# Main_Display_Module_ESP32.net
KiCad netlist of a schematic drawn in Altium Designer
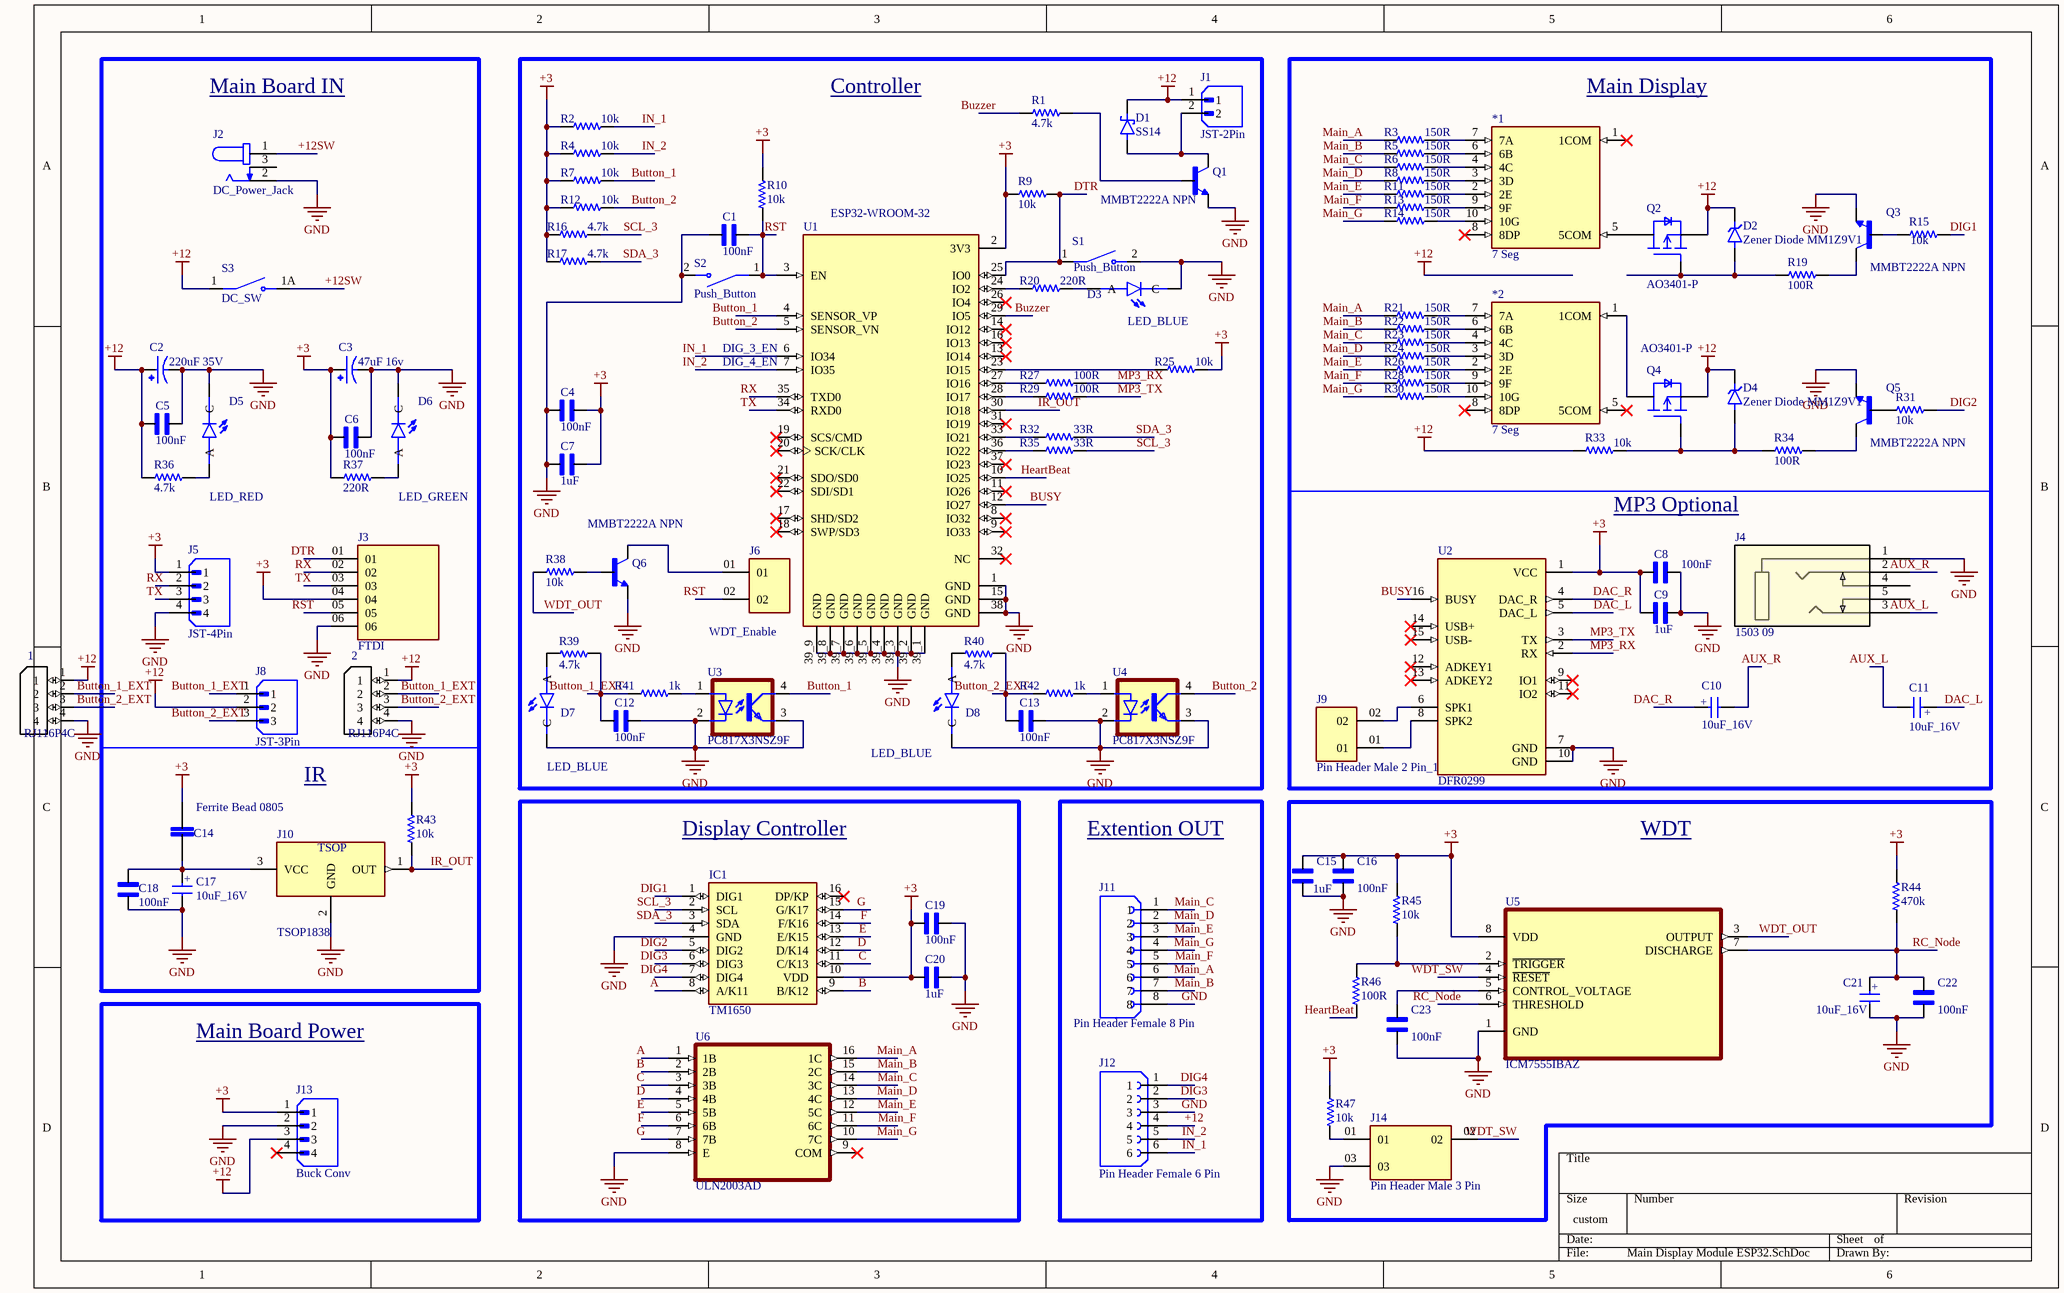
[diagram p0: Main Display Module ESP32.SchDoc]

(export (version "E")
  (design (tool "Eeschema 10.0.6"))
  (components
    (comp (ref "*1") (value "7 Seg") (footprint "2.3_7-SEG_DIS") (libsource (lib "Modules") (part "7 Seg")))
    (comp (ref "*2") (value "7 Seg") (footprint "2.3_7-SEG_DIS") (libsource (lib "Modules") (part "7 Seg")))
    (comp (ref "1")
      (value "RJ116P4C")
      (footprint "*RJ6P4C")
      (fields (field (name "MF") "TE Connectivity / Raychem") (field (name "MP") "RJ11-6P4C"))
      (libsource (lib "RJ116P4C") (part "RJ116P4C"))
    )
    (comp (ref "2")
      (value "RJ116P4C")
      (footprint "*RJ6P4C")
      (fields (field (name "MF") "TE Connectivity / Raychem") (field (name "MP") "RJ11-6P4C"))
      (libsource (lib "RJ116P4C") (part "RJ116P4C"))
    )
    (comp (ref "C1")
      (value "100nF")
      (footprint "Capacitor 0805")
      (description "0.1 ÂµF Â±10% 50V Ceramic Capacitor X7R 0805 (2012 Metric)")
      (fields (field (name "MF") "Murata") (field (name "MP") "GCE21BR71H104KA01L"))
      (libsource (lib "") (part "Capacitor 0805_1"))
    )
    (comp (ref "C2")
      (value "220uF 35V")
      (footprint "220uF 35V")
      (description "220ÂµF 35V Aluminum Electrolytic Capacitors Radial, Can - SMD 2000 Hrs @ 85Â°C")
      (fields (field (name "MP") "EEE1VA221P") (field (name "MF") "Panasonic"))
      (libsource (lib "Capacitors") (part "220uF 35V"))
    )
    (comp (ref "C3")
      (value "47uF 16v")
      (footprint "47uf 16v")
      (description "47ÂµF 16V Aluminum Electrolytic Capacitors Radial, Can - SMD 1000 Hrs @ 105Â°C")
      (fields (field (name "MF") "Panasonic") (field (name "MP") "EEE-HA1C470P"))
      (libsource (lib "Capacitors") (part "47uF 16v"))
    )
    (comp (ref "C4")
      (value "100nF")
      (footprint "Capacitor 0805")
      (description "0.1 ÂµF Â±10% 50V Ceramic Capacitor X7R 0805 (2012 Metric)")
      (fields (field (name "MF") "Murata") (field (name "MP") "GCE21BR71H104KA01L"))
      (libsource (lib "") (part "Capacitor 0805_1"))
    )
    (comp (ref "C5")
      (value "100nF")
      (footprint "Capacitor 0805")
      (description "0.1 ÂµF Â±10% 50V Ceramic Capacitor X7R 0805 (2012 Metric)")
      (fields (field (name "MF") "Murata") (field (name "MP") "GCE21BR71H104KA01L"))
      (libsource (lib "") (part "Capacitor 0805_1"))
    )
    (comp (ref "C6")
      (value "100nF")
      (footprint "Capacitor 0805")
      (description "0.1 ÂµF Â±10% 50V Ceramic Capacitor X7R 0805 (2012 Metric)")
      (fields (field (name "MF") "Murata") (field (name "MP") "GCE21BR71H104KA01L"))
      (libsource (lib "") (part "Capacitor 0805_1"))
    )
    (comp (ref "C7")
      (value "1uF")
      (footprint "Capacitor 0805")
      (description "0.1 ÂµF Â±10% 50V Ceramic Capacitor X7R 0805 (2012 Metric)")
      (fields (field (name "MF") "Murata") (field (name "MP") "GCE21BR71H104KA01L"))
      (libsource (lib "") (part "Capacitor 0805_1"))
    )
    (comp (ref "C8")
      (value "100nF")
      (footprint "Capacitor 0805")
      (description "0.1 ÂµF Â±10% 50V Ceramic Capacitor X7R 0805 (2012 Metric)")
      (fields (field (name "MF") "Murata") (field (name "MP") "GCE21BR71H104KA01L"))
      (libsource (lib "") (part "Capacitor 0805_1"))
    )
    (comp (ref "C9")
      (value "1uF")
      (footprint "Capacitor 0805")
      (description "0.1 ÂµF Â±10% 50V Ceramic Capacitor X7R 0805 (2012 Metric)")
      (fields (field (name "MF") "Murata") (field (name "MP") "GCE21BR71H104KA01L"))
      (libsource (lib "") (part "Capacitor 0805_1"))
    )
    (comp (ref "C10")
      (value "10uF_16V")
      (footprint "10uF_16V")
      (fields (field (name "MF") "WÃ¼rth Elektronik") (field (name "MP") "865090368008"))
      (libsource (lib "Capacitors") (part "10uF_16V"))
    )
    (comp (ref "C11")
      (value "10uF_16V")
      (footprint "10uF_16V")
      (fields (field (name "MF") "WÃ¼rth Elektronik") (field (name "MP") "865090368008"))
      (libsource (lib "Capacitors") (part "10uF_16V"))
    )
    (comp (ref "C12")
      (value "100nF")
      (footprint "Capacitor 0805")
      (description "0.1 ÂµF Â±10% 50V Ceramic Capacitor X7R 0805 (2012 Metric)")
      (fields (field (name "MF") "Murata") (field (name "MP") "GCE21BR71H104KA01L"))
      (libsource (lib "Capacitors") (part "Capacitor 0805"))
    )
    (comp (ref "C13")
      (value "100nF")
      (footprint "Capacitor 0805")
      (description "0.1 ÂµF Â±10% 50V Ceramic Capacitor X7R 0805 (2012 Metric)")
      (fields (field (name "MF") "Murata") (field (name "MP") "GCE21BR71H104KA01L"))
      (libsource (lib "") (part "Capacitor 0805_1"))
    )
    (comp (ref "C14")
      (value "Ferrite Bead 0805")
      (footprint "Ferrite Bead 0805")
      (description "BLM Series 0805 1 kOhm 200 mA 0.45 DCR Surface Mount Ferrite Bead")
      (fields (field (name "MF") "Murata") (field (name "MP") "BLM21AH102SN1D"))
      (libsource (lib "Resistors") (part "Ferrite Bead 0805"))
    )
    (comp (ref "C15")
      (value "1uF")
      (footprint "Capacitor 0805")
      (description "0.1 ÂµF Â±10% 50V Ceramic Capacitor X7R 0805 (2012 Metric)")
      (fields (field (name "MF") "Murata") (field (name "MP") "GCE21BR71H104KA01L"))
      (libsource (lib "") (part "Capacitor 0805_2"))
    )
    (comp (ref "C16")
      (value "100nF")
      (footprint "Capacitor 0805")
      (description "0.1 ÂµF Â±10% 50V Ceramic Capacitor X7R 0805 (2012 Metric)")
      (fields (field (name "MF") "Murata") (field (name "MP") "GCE21BR71H104KA01L"))
      (libsource (lib "") (part "Capacitor 0805_2"))
    )
    (comp (ref "C17")
      (value "10uF_16V")
      (footprint "10uF_16V")
      (fields (field (name "MF") "WÃ¼rth Elektronik") (field (name "MP") "865090368008"))
      (libsource (lib "Capacitors") (part "10uF_16V"))
    )
    (comp (ref "C18")
      (value "100nF")
      (footprint "Capacitor 0805")
      (description "0.1 ÂµF Â±10% 50V Ceramic Capacitor X7R 0805 (2012 Metric)")
      (fields (field (name "MF") "Murata") (field (name "MP") "GCE21BR71H104KA01L"))
      (libsource (lib "") (part "Capacitor 0805_2"))
    )
    (comp (ref "C19")
      (value "100nF")
      (footprint "Capacitor 0805")
      (description "0.1 ÂµF Â±10% 50V Ceramic Capacitor X7R 0805 (2012 Metric)")
      (fields (field (name "MF") "Murata") (field (name "MP") "GCE21BR71H104KA01L"))
      (libsource (lib "") (part "Capacitor 0805_1"))
    )
    (comp (ref "C20")
      (value "1uF")
      (footprint "Capacitor 0805")
      (description "0.1 ÂµF Â±10% 50V Ceramic Capacitor X7R 0805 (2012 Metric)")
      (fields (field (name "MF") "Murata") (field (name "MP") "GCE21BR71H104KA01L"))
      (libsource (lib "") (part "Capacitor 0805_1"))
    )
    (comp (ref "C21")
      (value "10uF_16V")
      (footprint "10uF_16V")
      (fields (field (name "MF") "WÃ¼rth Elektronik") (field (name "MP") "865090368008"))
      (libsource (lib "Capacitors") (part "10uF_16V"))
    )
    (comp (ref "C22")
      (value "100nF")
      (footprint "Capacitor 0805")
      (description "0.1 ÂµF Â±10% 50V Ceramic Capacitor X7R 0805 (2012 Metric)")
      (fields (field (name "MF") "Murata") (field (name "MP") "GCE21BR71H104KA01L"))
      (libsource (lib "") (part "Capacitor 0805_2"))
    )
    (comp (ref "C23")
      (value "100nF")
      (footprint "Capacitor 0805")
      (description "0.1 ÂµF Â±10% 50V Ceramic Capacitor X7R 0805 (2012 Metric)")
      (fields (field (name "MF") "Murata") (field (name "MP") "GCE21BR71H104KA01L"))
      (libsource (lib "") (part "Capacitor 0805_2"))
    )
    (comp (ref "D1")
      (value "SS14")
      (footprint "SS14")
      (description "1A, 40V, Schottky Rectifier")
      (fields (field (name "MF") "Taiwan Semiconductor"))
      (libsource (lib "ICs") (part "SS14"))
    )
    (comp (ref "D2")
      (value "Zener Diode MM1Z9V1")
      (footprint "Zener 9.1V SOD123")
      (description "Zener Diode 3.9 V 500 mW Â±5% Surface Mount SOD-123")
      (fields (field (name "MF") "Diodes Inc.") (field (name "MP") "BZT52C3V9-7-F"))
      (libsource (lib "ICs") (part "Zener Diode MM1Z9V1"))
    )
    (comp (ref "D3")
      (value "LED_BLUE")
      (footprint "LED_0603")
      (description "SMD LED 0603 INGAN GREEN ¦ Dialight 597-3326-607F")
      (fields (field (name "MF") "Dialight") (field (name "MP") "597-3326-607F"))
      (libsource (lib "ICs") (part "LED_0603"))
    )
    (comp (ref "D4")
      (value "Zener Diode MM1Z9V1")
      (footprint "Zener 9.1V SOD123")
      (description "Zener Diode 3.9 V 500 mW Â±5% Surface Mount SOD-123")
      (fields (field (name "MF") "Diodes Inc.") (field (name "MP") "BZT52C3V9-7-F"))
      (libsource (lib "ICs") (part "Zener Diode MM1Z9V1"))
    )
    (comp (ref "D5")
      (value "LED_RED")
      (footprint "LED_0603")
      (description "SMD LED 0603 INGAN GREEN ¦ Dialight 597-3326-607F")
      (fields (field (name "MF") "Dialight") (field (name "MP") "597-3326-607F"))
      (libsource (lib "ICs") (part "LED_0603"))
    )
    (comp (ref "D6")
      (value "LED_GREEN")
      (footprint "LED_0603")
      (description "SMD LED 0603 INGAN GREEN ¦ Dialight 597-3326-607F")
      (fields (field (name "MF") "Dialight") (field (name "MP") "597-3326-607F"))
      (libsource (lib "ICs") (part "LED_0603"))
    )
    (comp (ref "D7")
      (value "LED_BLUE")
      (footprint "LED_0603")
      (description "SMD LED 0603 INGAN GREEN ¦ Dialight 597-3326-607F")
      (fields (field (name "MF") "Dialight") (field (name "MP") "597-3326-607F"))
      (libsource (lib "ICs") (part "LED_0603"))
    )
    (comp (ref "D8")
      (value "LED_BLUE")
      (footprint "LED_0603")
      (description "SMD LED 0603 INGAN GREEN ¦ Dialight 597-3326-607F")
      (fields (field (name "MF") "Dialight") (field (name "MP") "597-3326-607F"))
      (libsource (lib "ICs") (part "LED_0603"))
    )
    (comp (ref "IC1")
      (value "TM1650")
      (footprint "TM1650 SOIC127")
      (fields (field (name "MF") "tm"))
      (libsource (lib "ICs") (part "TM1650"))
    )
    (comp (ref "J1")
      (value "JST-2Pin")
      (footprint "JST-2Pin")
      (description "Connector Header Through Hole 2 position 0.098 (2.50mm)")
      (fields (field (name "MF") "JST Sales") (field (name "MP") "B2B-XH-A(LF)(SN)"))
      (libsource (lib "Connectors") (part "JST-2Pin"))
    )
    (comp (ref "J2")
      (value "DC_Power_Jack")
      (footprint "DC_Power_Jack")
      (description "Power Barrel Connector Jack 2.05mm ID (0.081), 5.50mm OD (0.217) Through Hole, Right Angle")
      (fields (field (name "MF") "Global Connector Technology") (field (name "MP") "DCJ200-10-A-K1-K"))
      (libsource (lib "Connectors") (part "DC_Power_Jack"))
    )
    (comp (ref "J3")
      (value "FTDI")
      (footprint "6Pin-M-Header_6MX1-254MM")
      (fields (field (name "MP") "MTSW-106-24-G-S-300"))
      (libsource (lib "Connectors") (part "Pin Header Male 6 Pin"))
    )
    (comp (ref "J4")
      (value "1503 09")
      (footprint "3.5mm_AUX")
      (description "Description")
      (fields (field (name "COPYRIGHT") "Copyright (C) 2025 Ultra Librarian. All rights reserved."))
      (libsource (lib "Connectors") (part "3.5mm_AUX"))
    )
    (comp (ref "J5")
      (value "JST-4Pin")
      (footprint "4Pin-M-Header_3MX1-254MM")
      (description "Connector Header Through Hole 4 position 0.098 (2.50mm)")
      (fields (field (name "MF") "JST Sales") (field (name "MP") "B4B-XH-A(LF)(SN)"))
      (libsource (lib "Connectors") (part "JST-4Pin"))
    )
    (comp (ref "J6")
      (value "WDT_Enable")
      (footprint "2Pin-M-Header_3MX1-254MM - duplicate")
      (fields (field (name "MP") "TSW-101-23-L-T"))
      (libsource (lib "Connectors") (part "Pin Header Male 2 Pin_1"))
    )
    (comp (ref "J8")
      (value "JST-3Pin")
      (footprint "JST-3Pin")
      (description "Connector Header Through Hole 3 position 0.098 (2.50mm)")
      (fields (field (name "MF") "JST Sales America Inc.") (field (name "MP") "B3B-XH-A (LF)(SN)"))
      (libsource (lib "Connectors") (part "JST-3Pin"))
    )
    (comp (ref "J9")
      (value "Pin Header Male 2 Pin_1")
      (footprint "2Pin-M-Header_3MX1-254MM - duplicate")
      (fields (field (name "MP") "TSW-101-23-L-T"))
      (libsource (lib "") (part "Pin Header Male 2 Pin_1_1"))
    )
    (comp (ref "J10")
      (value "TSOP1838")
      (footprint "TSOP1838")
      (description "IR Remote Receiver 38KHz 35m 3-Pin")
      (fields (field (name "MF") "Vishay"))
      (libsource (lib "ICs") (part "TSOP1838"))
    )
    (comp (ref "J11")
      (value "Pin Header Female 8 Pin")
      (footprint "8Pin-F-Header_8FX1-254MM")
      (description "Headers & Wire Housings 2.54MM 0.1 8-PIN FEMALE HEADER")
      (fields (field (name "MP") "8Fx1-254mm") (field (name "MF") "Gravitech"))
      (libsource (lib "Connectors") (part "Pin Header Female 8 Pin"))
    )
    (comp (ref "J12")
      (value "Pin Header Female 6 Pin")
      (footprint "6Pin-F-Header_6FX1-254MM")
      (description "6 Position Total Single Row 2.54 mm Pitch Straight Female Header")
      (fields (field (name "MF") "Sullins Connector Solutions") (field (name "MP") "PPTC061LFBNRC"))
      (libsource (lib "Connectors") (part "Pin Header Female 6 Pin"))
    )
    (comp (ref "J13")
      (value "Buck Conv")
      (footprint "Regulator Buck-Conv")
      (description "Connector Header Through Hole 4 position 0.098 (2.50mm)")
      (fields (field (name "MF") "JST Sales") (field (name "MP") "B4B-XH-A(LF)(SN)"))
      (libsource (lib "Regulators") (part "Buck Conv"))
    )
    (comp (ref "J14")
      (value "Pin Header Male 3 Pin")
      (footprint "3Pin-M-Header_3MX1-254MM - duplicate - duplicate")
      (fields (field (name "MP") "TSW-101-23-L-T"))
      (libsource (lib "Connectors") (part "Pin Header Male 3 Pin"))
    )
    (comp (ref "Q1")
      (value "MMBT2222A NPN")
      (footprint "NPN_SOT23")
      (description "Bipolar (BJT) Transistor NPN 40V 600mA 300MHz 310mW Surface Mount SOT-23-3")
      (fields (field (name "MF") "STMicroelectronics") (field (name "MP") "MMBT2222A"))
      (libsource (lib "") (part "MMBT2222A NPN_1"))
    )
    (comp (ref "Q2")
      (value "AO3401-P")
      (footprint "AO-3401-P-SOT23-3")
      (description "P-Channel 30 V 4A (Ta) 1.4W (Ta) Surface Mount SOT-23-3")
      (fields (field (name "MF") "Alpha & Omega Semiconductor") (field (name "MP") "AO3401"))
      (libsource (lib "ICs") (part "AO3401-P"))
    )
    (comp (ref "Q3")
      (value "MMBT2222A NPN")
      (footprint "NPN_SOT23")
      (description "Bipolar (BJT) Transistor NPN 40V 600mA 300MHz 310mW Surface Mount SOT-23-3")
      (fields (field (name "MF") "STMicroelectronics") (field (name "MP") "MMBT2222A"))
      (libsource (lib "ICs") (part "MMBT2222A NPN"))
    )
    (comp (ref "Q4")
      (value "AO3401-P")
      (footprint "AO-3401-P-SOT23-3")
      (description "P-Channel 30 V 4A (Ta) 1.4W (Ta) Surface Mount SOT-23-3")
      (fields (field (name "MF") "Alpha & Omega Semiconductor") (field (name "MP") "AO3401"))
      (libsource (lib "ICs") (part "AO3401-P"))
    )
    (comp (ref "Q5")
      (value "MMBT2222A NPN")
      (footprint "NPN_SOT23")
      (description "Bipolar (BJT) Transistor NPN 40V 600mA 300MHz 310mW Surface Mount SOT-23-3")
      (fields (field (name "MF") "STMicroelectronics") (field (name "MP") "MMBT2222A"))
      (libsource (lib "ICs") (part "MMBT2222A NPN"))
    )
    (comp (ref "Q6")
      (value "MMBT2222A NPN")
      (footprint "NPN_SOT23")
      (description "Bipolar (BJT) Transistor NPN 40V 600mA 300MHz 310mW Surface Mount SOT-23-3")
      (fields (field (name "MF") "STMicroelectronics") (field (name "MP") "MMBT2222A"))
      (libsource (lib "") (part "MMBT2222A NPN_1"))
    )
    (comp (ref "R1")
      (value "4.7k")
      (footprint "RES0603")
      (description "Fixed Resistor CRGCQ 1206 10K 5%")
      (fields (field (name "MF") "TE Connectivity") (field (name "MP") "CRGCQ1206J10K"))
      (libsource (lib "Resistors") (part "Resistor 0603"))
    )
    (comp (ref "R2")
      (value "10k")
      (footprint "RES0603")
      (description "Fixed Resistor CRGCQ 1206 10K 5%")
      (fields (field (name "MF") "TE Connectivity") (field (name "MP") "CRGCQ1206J10K"))
      (libsource (lib "Resistors") (part "Resistor 0603"))
    )
    (comp (ref "R3")
      (value "150R")
      (footprint "Resistor 1206")
      (description "Fixed Resistor CRGCQ 1206 10K 5%")
      (fields (field (name "MF") "TE Connectivity") (field (name "MP") "CRGCQ1206J10K"))
      (libsource (lib "Resistors") (part "Resistor 1206"))
    )
    (comp (ref "R4")
      (value "10k")
      (footprint "RES0603")
      (description "Fixed Resistor CRGCQ 1206 10K 5%")
      (fields (field (name "MF") "TE Connectivity") (field (name "MP") "CRGCQ1206J10K"))
      (libsource (lib "Resistors") (part "Resistor 0603"))
    )
    (comp (ref "R5")
      (value "150R")
      (footprint "Resistor 1206")
      (description "Fixed Resistor CRGCQ 1206 10K 5%")
      (fields (field (name "MF") "TE Connectivity") (field (name "MP") "CRGCQ1206J10K"))
      (libsource (lib "Resistors") (part "Resistor 1206"))
    )
    (comp (ref "R6")
      (value "150R")
      (footprint "Resistor 1206")
      (description "Fixed Resistor CRGCQ 1206 10K 5%")
      (fields (field (name "MF") "TE Connectivity") (field (name "MP") "CRGCQ1206J10K"))
      (libsource (lib "Resistors") (part "Resistor 1206"))
    )
    (comp (ref "R7")
      (value "10k")
      (footprint "RES0603")
      (description "Fixed Resistor CRGCQ 1206 10K 5%")
      (fields (field (name "MF") "TE Connectivity") (field (name "MP") "CRGCQ1206J10K"))
      (libsource (lib "Resistors") (part "Resistor 0603"))
    )
    (comp (ref "R8")
      (value "150R")
      (footprint "Resistor 1206")
      (description "Fixed Resistor CRGCQ 1206 10K 5%")
      (fields (field (name "MF") "TE Connectivity") (field (name "MP") "CRGCQ1206J10K"))
      (libsource (lib "Resistors") (part "Resistor 1206"))
    )
    (comp (ref "R9")
      (value "10k")
      (footprint "RES0603")
      (description "Fixed Resistor CRGCQ 1206 10K 5%")
      (fields (field (name "MF") "TE Connectivity") (field (name "MP") "CRGCQ1206J10K"))
      (libsource (lib "Resistors") (part "Resistor 0603"))
    )
    (comp (ref "R10")
      (value "10k")
      (footprint "RES0603")
      (description "Fixed Resistor CRGCQ 1206 10K 5%")
      (fields (field (name "MF") "TE Connectivity") (field (name "MP") "CRGCQ1206J10K"))
      (libsource (lib "Resistors") (part "Resistor 0603"))
    )
    (comp (ref "R11")
      (value "150R")
      (footprint "Resistor 1206")
      (description "Fixed Resistor CRGCQ 1206 10K 5%")
      (fields (field (name "MF") "TE Connectivity") (field (name "MP") "CRGCQ1206J10K"))
      (libsource (lib "Resistors") (part "Resistor 1206"))
    )
    (comp (ref "R12")
      (value "10k")
      (footprint "RES0603")
      (description "Fixed Resistor CRGCQ 1206 10K 5%")
      (fields (field (name "MF") "TE Connectivity") (field (name "MP") "CRGCQ1206J10K"))
      (libsource (lib "Resistors") (part "Resistor 0603"))
    )
    (comp (ref "R13")
      (value "150R")
      (footprint "Resistor 1206")
      (description "Fixed Resistor CRGCQ 1206 10K 5%")
      (fields (field (name "MF") "TE Connectivity") (field (name "MP") "CRGCQ1206J10K"))
      (libsource (lib "Resistors") (part "Resistor 1206"))
    )
    (comp (ref "R14")
      (value "150R")
      (footprint "Resistor 1206")
      (description "Fixed Resistor CRGCQ 1206 10K 5%")
      (fields (field (name "MF") "TE Connectivity") (field (name "MP") "CRGCQ1206J10K"))
      (libsource (lib "Resistors") (part "Resistor 1206"))
    )
    (comp (ref "R15")
      (value "10k")
      (footprint "RES0603")
      (description "Fixed Resistor CRGCQ 1206 10K 5%")
      (fields (field (name "MF") "TE Connectivity") (field (name "MP") "CRGCQ1206J10K"))
      (libsource (lib "Resistors") (part "Resistor 0603"))
    )
    (comp (ref "R16")
      (value "4.7k")
      (footprint "RES0603")
      (description "Fixed Resistor CRGCQ 1206 10K 5%")
      (fields (field (name "MF") "TE Connectivity") (field (name "MP") "CRGCQ1206J10K"))
      (libsource (lib "Resistors") (part "Resistor 0603"))
    )
    (comp (ref "R17")
      (value "4.7k")
      (footprint "RES0603")
      (description "Fixed Resistor CRGCQ 1206 10K 5%")
      (fields (field (name "MF") "TE Connectivity") (field (name "MP") "CRGCQ1206J10K"))
      (libsource (lib "Resistors") (part "Resistor 0603"))
    )
    (comp (ref "R19")
      (value "100R")
      (footprint "RES0603")
      (description "Fixed Resistor CRGCQ 1206 10K 5%")
      (fields (field (name "MF") "TE Connectivity") (field (name "MP") "CRGCQ1206J10K"))
      (libsource (lib "Resistors") (part "Resistor 0603"))
    )
    (comp (ref "R20")
      (value "220R")
      (footprint "RES0603")
      (description "Fixed Resistor CRGCQ 1206 10K 5%")
      (fields (field (name "MF") "TE Connectivity") (field (name "MP") "CRGCQ1206J10K"))
      (libsource (lib "Resistors") (part "Resistor 0603"))
    )
    (comp (ref "R21")
      (value "150R")
      (footprint "Resistor 1206")
      (description "Fixed Resistor CRGCQ 1206 10K 5%")
      (fields (field (name "MF") "TE Connectivity") (field (name "MP") "CRGCQ1206J10K"))
      (libsource (lib "Resistors") (part "Resistor 1206"))
    )
    (comp (ref "R22")
      (value "150R")
      (footprint "Resistor 1206")
      (description "Fixed Resistor CRGCQ 1206 10K 5%")
      (fields (field (name "MF") "TE Connectivity") (field (name "MP") "CRGCQ1206J10K"))
      (libsource (lib "Resistors") (part "Resistor 1206"))
    )
    (comp (ref "R23")
      (value "150R")
      (footprint "Resistor 1206")
      (description "Fixed Resistor CRGCQ 1206 10K 5%")
      (fields (field (name "MF") "TE Connectivity") (field (name "MP") "CRGCQ1206J10K"))
      (libsource (lib "Resistors") (part "Resistor 1206"))
    )
    (comp (ref "R24")
      (value "150R")
      (footprint "Resistor 1206")
      (description "Fixed Resistor CRGCQ 1206 10K 5%")
      (fields (field (name "MF") "TE Connectivity") (field (name "MP") "CRGCQ1206J10K"))
      (libsource (lib "Resistors") (part "Resistor 1206"))
    )
    (comp (ref "R25")
      (value "10k")
      (footprint "RES0603")
      (description "Fixed Resistor CRGCQ 1206 10K 5%")
      (fields (field (name "MF") "TE Connectivity") (field (name "MP") "CRGCQ1206J10K"))
      (libsource (lib "Resistors") (part "Resistor 0603"))
    )
    (comp (ref "R26")
      (value "150R")
      (footprint "Resistor 1206")
      (description "Fixed Resistor CRGCQ 1206 10K 5%")
      (fields (field (name "MF") "TE Connectivity") (field (name "MP") "CRGCQ1206J10K"))
      (libsource (lib "Resistors") (part "Resistor 1206"))
    )
    (comp (ref "R27")
      (value "100R")
      (footprint "RES0603")
      (description "Fixed Resistor CRGCQ 1206 10K 5%")
      (fields (field (name "MF") "TE Connectivity") (field (name "MP") "CRGCQ1206J10K"))
      (libsource (lib "Resistors") (part "Resistor 0603"))
    )
    (comp (ref "R28")
      (value "150R")
      (footprint "Resistor 1206")
      (description "Fixed Resistor CRGCQ 1206 10K 5%")
      (fields (field (name "MF") "TE Connectivity") (field (name "MP") "CRGCQ1206J10K"))
      (libsource (lib "Resistors") (part "Resistor 1206"))
    )
    (comp (ref "R29")
      (value "100R")
      (footprint "RES0603")
      (description "Fixed Resistor CRGCQ 1206 10K 5%")
      (fields (field (name "MF") "TE Connectivity") (field (name "MP") "CRGCQ1206J10K"))
      (libsource (lib "Resistors") (part "Resistor 0603"))
    )
    (comp (ref "R30")
      (value "150R")
      (footprint "Resistor 1206")
      (description "Fixed Resistor CRGCQ 1206 10K 5%")
      (fields (field (name "MF") "TE Connectivity") (field (name "MP") "CRGCQ1206J10K"))
      (libsource (lib "Resistors") (part "Resistor 1206"))
    )
    (comp (ref "R31")
      (value "10k")
      (footprint "RES0603")
      (description "Fixed Resistor CRGCQ 1206 10K 5%")
      (fields (field (name "MF") "TE Connectivity") (field (name "MP") "CRGCQ1206J10K"))
      (libsource (lib "Resistors") (part "Resistor 0603"))
    )
    (comp (ref "R32")
      (value "33R")
      (footprint "RES0603")
      (description "Fixed Resistor CRGCQ 1206 10K 5%")
      (fields (field (name "MF") "TE Connectivity") (field (name "MP") "CRGCQ1206J10K"))
      (libsource (lib "Resistors") (part "Resistor 0603"))
    )
    (comp (ref "R33")
      (value "10k")
      (footprint "RES0603")
      (description "Fixed Resistor CRGCQ 1206 10K 5%")
      (fields (field (name "MF") "TE Connectivity") (field (name "MP") "CRGCQ1206J10K"))
      (libsource (lib "Resistors") (part "Resistor 0603"))
    )
    (comp (ref "R34")
      (value "100R")
      (footprint "RES0603")
      (description "Fixed Resistor CRGCQ 1206 10K 5%")
      (fields (field (name "MF") "TE Connectivity") (field (name "MP") "CRGCQ1206J10K"))
      (libsource (lib "Resistors") (part "Resistor 0603"))
    )
    (comp (ref "R35")
      (value "33R")
      (footprint "RES0603")
      (description "Fixed Resistor CRGCQ 1206 10K 5%")
      (fields (field (name "MF") "TE Connectivity") (field (name "MP") "CRGCQ1206J10K"))
      (libsource (lib "Resistors") (part "Resistor 0603"))
    )
    (comp (ref "R36")
      (value "4.7k")
      (footprint "RES0603")
      (description "Fixed Resistor CRGCQ 1206 10K 5%")
      (fields (field (name "MF") "TE Connectivity") (field (name "MP") "CRGCQ1206J10K"))
      (libsource (lib "Resistors") (part "Resistor 0603"))
    )
    (comp (ref "R37")
      (value "220R")
      (footprint "RES0603")
      (description "Fixed Resistor CRGCQ 1206 10K 5%")
      (fields (field (name "MF") "TE Connectivity") (field (name "MP") "CRGCQ1206J10K"))
      (libsource (lib "Resistors") (part "Resistor 0603"))
    )
    (comp (ref "R38")
      (value "10k")
      (footprint "RES0603")
      (description "Fixed Resistor CRGCQ 1206 10K 5%")
      (fields (field (name "MF") "TE Connectivity") (field (name "MP") "CRGCQ1206J10K"))
      (libsource (lib "Resistors") (part "Resistor 0603"))
    )
    (comp (ref "R39")
      (value "4.7k")
      (footprint "RES0603")
      (description "Fixed Resistor CRGCQ 1206 10K 5%")
      (fields (field (name "MF") "TE Connectivity") (field (name "MP") "CRGCQ1206J10K"))
      (libsource (lib "Resistors") (part "Resistor 0603"))
    )
    (comp (ref "R40")
      (value "4.7k")
      (footprint "RES0603")
      (description "Fixed Resistor CRGCQ 1206 10K 5%")
      (fields (field (name "MF") "TE Connectivity") (field (name "MP") "CRGCQ1206J10K"))
      (libsource (lib "Resistors") (part "Resistor 0603"))
    )
    (comp (ref "R41")
      (value "1k")
      (footprint "RES0603")
      (description "Fixed Resistor CRGCQ 1206 10K 5%")
      (fields (field (name "MF") "TE Connectivity") (field (name "MP") "CRGCQ1206J10K"))
      (libsource (lib "Resistors") (part "Resistor 0603"))
    )
    (comp (ref "R42")
      (value "1k")
      (footprint "RES0603")
      (description "Fixed Resistor CRGCQ 1206 10K 5%")
      (fields (field (name "MF") "TE Connectivity") (field (name "MP") "CRGCQ1206J10K"))
      (libsource (lib "Resistors") (part "Resistor 0603"))
    )
    (comp (ref "R43")
      (value "10k")
      (footprint "RES0603")
      (description "Fixed Resistor CRGCQ 1206 10K 5%")
      (fields (field (name "MF") "TE Connectivity") (field (name "MP") "CRGCQ1206J10K"))
      (libsource (lib "Resistors") (part "Resistor 0603"))
    )
    (comp (ref "R44")
      (value "470k")
      (footprint "RES0603")
      (description "Fixed Resistor CRGCQ 1206 10K 5%")
      (fields (field (name "MF") "TE Connectivity") (field (name "MP") "CRGCQ1206J10K"))
      (libsource (lib "Resistors") (part "Resistor 0603"))
    )
    (comp (ref "R45")
      (value "10k")
      (footprint "RES0603")
      (description "Fixed Resistor CRGCQ 1206 10K 5%")
      (fields (field (name "MF") "TE Connectivity") (field (name "MP") "CRGCQ1206J10K"))
      (libsource (lib "Resistors") (part "Resistor 0603"))
    )
    (comp (ref "R46")
      (value "100R")
      (footprint "RES0603")
      (description "Fixed Resistor CRGCQ 1206 10K 5%")
      (fields (field (name "MF") "TE Connectivity") (field (name "MP") "CRGCQ1206J10K"))
      (libsource (lib "Resistors") (part "Resistor 0603"))
    )
    (comp (ref "R47")
      (value "10k")
      (footprint "RES0603")
      (description "Fixed Resistor CRGCQ 1206 10K 5%")
      (fields (field (name "MF") "TE Connectivity") (field (name "MP") "CRGCQ1206J10K"))
      (libsource (lib "Resistors") (part "Resistor 0603"))
    )
    (comp (ref "S1")
      (value "Push_Button")
      (footprint "Push_Button")
      (description "SWITCH TACTILE SPST-NO 0.05A 12V")
      (fields (field (name "MF") "E-Switch") (field (name "MP") "TL1107BF130WQ"))
      (libsource (lib "Connectors") (part "Push_Button"))
    )
    (comp (ref "S2")
      (value "Push_Button")
      (footprint "Push_Button")
      (description "SWITCH TACTILE SPST-NO 0.05A 12V")
      (fields (field (name "MF") "E-Switch") (field (name "MP") "TL1107BF130WQ"))
      (libsource (lib "Connectors") (part "Push_Button"))
    )
    (comp (ref "S3")
      (value "DC_SW")
      (footprint "DC_SW")
      (fields (field (name "MF") "E-Switch") (field (name "MP") "R1966ABLKBLKFR"))
      (libsource (lib "Connectors") (part "DC_SW"))
    )
    (comp (ref "U1")
      (value "ESP32-WROOM-32")
      (footprint "MODULE_ESP32-WROOM-32")
      (fields (field (name "MF") "Espressif Systems"))
      (libsource (lib "ICs") (part "ESP32-WROOM-32"))
    )
    (comp (ref "U2")
      (value "DFR0299")
      (footprint "MODULE_DFR0299_DIP")
      (description "- MP3 Player Audio Arduino Platform Evaluation Expansion Board")
      (fields (field (name "MF") "DFRobot"))
      (libsource (lib "ICs") (part "DFR0299"))
    )
    (comp (ref "U3")
      (value "PC817X3NSZ9F")
      (footprint "PC 817")
      (description "Optoisolator Transistor Output 5000Vrms 1 Channel 4-DIP")
      (fields (field (name "MF") "Sharp Microelectronics"))
      (libsource (lib "ICs") (part "PC817X3NSZ9F"))
    )
    (comp (ref "U4")
      (value "PC817X3NSZ9F")
      (footprint "PC 817")
      (description "Optoisolator Transistor Output 5000Vrms 1 Channel 4-DIP")
      (fields (field (name "MF") "Sharp Microelectronics"))
      (libsource (lib "ICs") (part "PC817X3NSZ9F"))
    )
    (comp (ref "U5")
      (value "ICM7555IBAZ")
      (footprint "ICM7555")
      (description "555 Type, Timer/Oscillator (Single) IC 1MHz 8-SOIC")
      (fields (field (name "MF") "Renesas Electronics America Inc"))
      (libsource (lib "ICs") (part "ICM7555IBAZ"))
    )
    (comp (ref "U6")
      (value "ULN2003AD")
      (footprint "ULN 2003 SOIC127P600X175-16N")
      (description "50-V, 7-ch darlington transistor array, -20C to 70C")
      (fields (field (name "MF") "Texas Instruments"))
      (libsource (lib "ICs") (part "ULN2003AD"))
    )
  )
  (nets
    (net (code "1") (name "+3") (class "Default")
      (node (ref "C14") (pin "2") (pinfunction "2_2") (pintype "passive"))
      (node (ref "C15") (pin "2") (pinfunction "2_2") (pintype "passive"))
      (node (ref "C16") (pin "2") (pinfunction "2_2") (pintype "passive"))
      (node (ref "C19") (pin "1") (pinfunction "1_1") (pintype "passive"))
      (node (ref "C20") (pin "1") (pinfunction "1_1") (pintype "passive"))
      (node (ref "C3") (pin "1") (pinfunction "1_1") (pintype "passive"))
      (node (ref "C4") (pin "2") (pinfunction "2_2") (pintype "passive"))
      (node (ref "C6") (pin "1") (pinfunction "1_1") (pintype "passive"))
      (node (ref "C7") (pin "2") (pinfunction "2_2") (pintype "passive"))
      (node (ref "C8") (pin "1") (pinfunction "1_1") (pintype "passive"))
      (node (ref "C9") (pin "1") (pinfunction "1_1") (pintype "passive"))
      (node (ref "IC1") (pin "10") (pinfunction "VDD_10") (pintype "power_in"))
      (node (ref "J13") (pin "1") (pinfunction "1_1") (pintype "passive"))
      (node (ref "J3") (pin "04") (pinfunction "04_04") (pintype "passive"))
      (node (ref "J5") (pin "1") (pinfunction "1_1") (pintype "passive"))
      (node (ref "R10") (pin "2") (pinfunction "2_2") (pintype "passive"))
      (node (ref "R12") (pin "1") (pinfunction "1_1") (pintype "passive"))
      (node (ref "R16") (pin "1") (pinfunction "1_1") (pintype "passive"))
      (node (ref "R17") (pin "1") (pinfunction "1_1") (pintype "passive"))
      (node (ref "R2") (pin "1") (pinfunction "1_1") (pintype "passive"))
      (node (ref "R25") (pin "2") (pinfunction "2_2") (pintype "passive"))
      (node (ref "R37") (pin "1") (pinfunction "1_1") (pintype "passive"))
      (node (ref "R4") (pin "1") (pinfunction "1_1") (pintype "passive"))
      (node (ref "R43") (pin "2") (pinfunction "2_2") (pintype "passive"))
      (node (ref "R44") (pin "2") (pinfunction "2_2") (pintype "passive"))
      (node (ref "R45") (pin "2") (pinfunction "2_2") (pintype "passive"))
      (node (ref "R47") (pin "1") (pinfunction "1_1") (pintype "passive"))
      (node (ref "R7") (pin "1") (pinfunction "1_1") (pintype "passive"))
      (node (ref "R9") (pin "1") (pinfunction "1_1") (pintype "passive"))
      (node (ref "U1") (pin "2") (pinfunction "3V3_2") (pintype "power_in"))
      (node (ref "U2") (pin "1") (pinfunction "VCC_1") (pintype "power_in"))
      (node (ref "U5") (pin "8") (pinfunction "VDD_8") (pintype "power_in"))
    )
    (net (code "2") (name "+12") (class "Default")
      (node (ref "1") (pin "1") (pinfunction "1_1") (pintype "bidirectional"))
      (node (ref "2") (pin "1") (pinfunction "1_1") (pintype "bidirectional"))
      (node (ref "C2") (pin "1") (pinfunction "1_1") (pintype "passive"))
      (node (ref "C5") (pin "1") (pinfunction "1_1") (pintype "passive"))
      (node (ref "D1") (pin "C") (pinfunction "K_C") (pintype "passive"))
      (node (ref "D2") (pin "C") (pinfunction "C_C") (pintype "passive"))
      (node (ref "D4") (pin "C") (pinfunction "C_C") (pintype "passive"))
      (node (ref "J1") (pin "1") (pinfunction "1_1") (pintype "passive"))
      (node (ref "J12") (pin "4") (pinfunction "4_4") (pintype "passive"))
      (node (ref "J13") (pin "3") (pinfunction "3_3") (pintype "passive"))
      (node (ref "J8") (pin "2") (pinfunction "2_2") (pintype "passive"))
      (node (ref "Q2") (pin "2") (pinfunction "S_2") (pintype "passive"))
      (node (ref "Q4") (pin "2") (pinfunction "S_2") (pintype "passive"))
      (node (ref "R33") (pin "1") (pinfunction "1_1") (pintype "passive"))
      (node (ref "R36") (pin "1") (pinfunction "1_1") (pintype "passive"))
      (node (ref "S3") (pin "1") (pinfunction "1_1") (pintype "passive"))
    )
    (net (code "3") (name "/+12SW") (class "Default")
      (node (ref "J2") (pin "1") (pinfunction "1_1") (pintype "passive"))
      (node (ref "S3") (pin "1A") (pinfunction "1A_1A") (pintype "passive"))
    )
    (net (code "4") (name "/A") (class "Default")
      (node (ref "IC1") (pin "8") (pinfunction "A/K11_8") (pintype "bidirectional"))
      (node (ref "U6") (pin "1") (pinfunction "1B_1") (pintype "input"))
    )
    (net (code "5") (name "/AUX_L") (class "Default")
      (node (ref "C11") (pin "2") (pinfunction "NEG_2") (pintype "passive"))
      (node (ref "J4") (pin "3") (pinfunction "3_3") (pintype "passive"))
    )
    (net (code "6") (name "/AUX_R") (class "Default")
      (node (ref "C10") (pin "2") (pinfunction "NEG_2") (pintype "passive"))
      (node (ref "J4") (pin "2") (pinfunction "2_2") (pintype "passive"))
    )
    (net (code "7") (name "/B") (class "Default")
      (node (ref "IC1") (pin "9") (pinfunction "B/K12_9") (pintype "bidirectional"))
      (node (ref "U6") (pin "2") (pinfunction "2B_2") (pintype "input"))
    )
    (net (code "8") (name "/BUSY") (class "Default")
      (node (ref "U1") (pin "12") (pinfunction "IO27_12") (pintype "bidirectional"))
      (node (ref "U2") (pin "16") (pinfunction "BUSY_16") (pintype "input"))
    )
    (net (code "9") (name "/Button_1") (class "Default")
      (node (ref "R7") (pin "2") (pinfunction "2_2") (pintype "passive"))
      (node (ref "U1") (pin "4") (pinfunction "SENSOR_VP_4") (pintype "input"))
      (node (ref "U3") (pin "4") (pinfunction "COL_4") (pintype "passive"))
    )
    (net (code "10") (name "/Button_1_EXT") (class "Default")
      (node (ref "1") (pin "2") (pinfunction "2_2") (pintype "bidirectional"))
      (node (ref "2") (pin "2") (pinfunction "2_2") (pintype "bidirectional"))
      (node (ref "C12") (pin "2") (pinfunction "2_2") (pintype "passive"))
      (node (ref "J8") (pin "1") (pinfunction "1_1") (pintype "passive"))
      (node (ref "R39") (pin "1") (pinfunction "1_1") (pintype "passive"))
      (node (ref "R41") (pin "1") (pinfunction "1_1") (pintype "passive"))
    )
    (net (code "11") (name "/Button_2") (class "Default")
      (node (ref "R12") (pin "2") (pinfunction "2_2") (pintype "passive"))
      (node (ref "U1") (pin "5") (pinfunction "SENSOR_VN_5") (pintype "input"))
      (node (ref "U4") (pin "4") (pinfunction "COL_4") (pintype "passive"))
    )
    (net (code "12") (name "/Button_2_EXT") (class "Default")
      (node (ref "1") (pin "3") (pinfunction "3_3") (pintype "bidirectional"))
      (node (ref "2") (pin "3") (pinfunction "3_3") (pintype "bidirectional"))
      (node (ref "C13") (pin "1") (pinfunction "1_1") (pintype "passive"))
      (node (ref "J8") (pin "3") (pinfunction "3_3") (pintype "passive"))
      (node (ref "R40") (pin "1") (pinfunction "1_1") (pintype "passive"))
      (node (ref "R42") (pin "1") (pinfunction "1_1") (pintype "passive"))
    )
    (net (code "13") (name "/Buzzer") (class "Default")
      (node (ref "R1") (pin "1") (pinfunction "1_1") (pintype "passive"))
      (node (ref "U1") (pin "29") (pinfunction "IO5_29") (pintype "bidirectional"))
    )
    (net (code "14") (name "/C") (class "Default")
      (node (ref "IC1") (pin "11") (pinfunction "C/K13_11") (pintype "bidirectional"))
      (node (ref "U6") (pin "3") (pinfunction "3B_3") (pintype "input"))
    )
    (net (code "15") (name "/D") (class "Default")
      (node (ref "IC1") (pin "12") (pinfunction "D/K14_12") (pintype "bidirectional"))
      (node (ref "U6") (pin "4") (pinfunction "4B_4") (pintype "input"))
    )
    (net (code "16") (name "/DAC_L") (class "Default")
      (node (ref "C11") (pin "1") (pinfunction "POS_1") (pintype "passive"))
      (node (ref "U2") (pin "5") (pinfunction "DAC_L_5") (pintype "output"))
    )
    (net (code "17") (name "/DAC_R") (class "Default")
      (node (ref "C10") (pin "1") (pinfunction "POS_1") (pintype "passive"))
      (node (ref "U2") (pin "4") (pinfunction "DAC_R_4") (pintype "output"))
    )
    (net (code "18") (name "/DIG1") (class "Default")
      (node (ref "IC1") (pin "1") (pinfunction "DIG1_1") (pintype "bidirectional"))
      (node (ref "R15") (pin "2") (pinfunction "2_2") (pintype "passive"))
    )
    (net (code "19") (name "/DIG2") (class "Default")
      (node (ref "IC1") (pin "5") (pinfunction "DIG2_5") (pintype "bidirectional"))
      (node (ref "R31") (pin "2") (pinfunction "2_2") (pintype "passive"))
    )
    (net (code "20") (name "/DIG3") (class "Default")
      (node (ref "IC1") (pin "6") (pinfunction "DIG3_6") (pintype "bidirectional"))
      (node (ref "J12") (pin "2") (pinfunction "2_2") (pintype "passive"))
    )
    (net (code "21") (name "/DIG4") (class "Default")
      (node (ref "IC1") (pin "7") (pinfunction "DIG4_7") (pintype "bidirectional"))
      (node (ref "J12") (pin "1") (pinfunction "1_1") (pintype "passive"))
    )
    (net (code "22") (name "/DTR") (class "Default")
      (node (ref "J3") (pin "01") (pinfunction "01_01") (pintype "passive"))
      (node (ref "R9") (pin "2") (pinfunction "2_2") (pintype "passive"))
      (node (ref "S1") (pin "1") (pinfunction "1_1") (pintype "passive"))
      (node (ref "U1") (pin "25") (pinfunction "IO0_25") (pintype "bidirectional"))
    )
    (net (code "23") (name "/E") (class "Default")
      (node (ref "IC1") (pin "13") (pinfunction "E/K15_13") (pintype "bidirectional"))
      (node (ref "U6") (pin "5") (pinfunction "5B_5") (pintype "input"))
    )
    (net (code "24") (name "/F") (class "Default")
      (node (ref "IC1") (pin "14") (pinfunction "F/K16_14") (pintype "bidirectional"))
      (node (ref "U6") (pin "6") (pinfunction "6B_6") (pintype "input"))
    )
    (net (code "25") (name "/G") (class "Default")
      (node (ref "IC1") (pin "15") (pinfunction "G/K17_15") (pintype "bidirectional"))
      (node (ref "U6") (pin "7") (pinfunction "7B_7") (pintype "input"))
    )
    (net (code "26") (name "/HeartBeat") (class "Default")
      (node (ref "R46") (pin "1") (pinfunction "1_1") (pintype "passive"))
      (node (ref "U1") (pin "10") (pinfunction "IO25_10") (pintype "bidirectional"))
    )
    (net (code "27") (name "/IN_1") (class "Default")
      (node (ref "J12") (pin "6") (pinfunction "6_6") (pintype "passive"))
      (node (ref "R2") (pin "2") (pinfunction "2_2") (pintype "passive"))
      (node (ref "U1") (pin "6") (pinfunction "IO34_6") (pintype "input"))
    )
    (net (code "28") (name "/IN_2") (class "Default")
      (node (ref "J12") (pin "5") (pinfunction "5_5") (pintype "passive"))
      (node (ref "R4") (pin "2") (pinfunction "2_2") (pintype "passive"))
      (node (ref "U1") (pin "7") (pinfunction "IO35_7") (pintype "input"))
    )
    (net (code "29") (name "/IR_OUT") (class "Default")
      (node (ref "J10") (pin "1") (pinfunction "OUT_1") (pintype "output"))
      (node (ref "R43") (pin "1") (pinfunction "1_1") (pintype "passive"))
      (node (ref "U1") (pin "30") (pinfunction "IO18_30") (pintype "bidirectional"))
    )
    (net (code "30") (name "/MP3_RX") (class "Default")
      (node (ref "R27") (pin "2") (pinfunction "2_2") (pintype "passive"))
      (node (ref "U2") (pin "2") (pinfunction "RX_2") (pintype "input"))
    )
    (net (code "31") (name "/MP3_TX") (class "Default")
      (node (ref "R29") (pin "2") (pinfunction "2_2") (pintype "passive"))
      (node (ref "U2") (pin "3") (pinfunction "TX_3") (pintype "output"))
    )
    (net (code "32") (name "/Main_A") (class "Default")
      (node (ref "J11") (pin "6") (pinfunction "6_6") (pintype "passive"))
      (node (ref "R21") (pin "1") (pinfunction "1_1") (pintype "passive"))
      (node (ref "R3") (pin "1") (pinfunction "1_1") (pintype "passive"))
      (node (ref "U6") (pin "16") (pinfunction "1C_16") (pintype "output"))
    )
    (net (code "33") (name "/Main_B") (class "Default")
      (node (ref "J11") (pin "7") (pinfunction "7_7") (pintype "passive"))
      (node (ref "R22") (pin "1") (pinfunction "1_1") (pintype "passive"))
      (node (ref "R5") (pin "1") (pinfunction "1_1") (pintype "passive"))
      (node (ref "U6") (pin "15") (pinfunction "2C_15") (pintype "output"))
    )
    (net (code "34") (name "/Main_C") (class "Default")
      (node (ref "J11") (pin "1") (pinfunction "1_1") (pintype "passive"))
      (node (ref "R23") (pin "1") (pinfunction "1_1") (pintype "passive"))
      (node (ref "R6") (pin "1") (pinfunction "1_1") (pintype "passive"))
      (node (ref "U6") (pin "14") (pinfunction "3C_14") (pintype "output"))
    )
    (net (code "35") (name "/Main_D") (class "Default")
      (node (ref "J11") (pin "2") (pinfunction "2_2") (pintype "passive"))
      (node (ref "R24") (pin "1") (pinfunction "1_1") (pintype "passive"))
      (node (ref "R8") (pin "1") (pinfunction "1_1") (pintype "passive"))
      (node (ref "U6") (pin "13") (pinfunction "4C_13") (pintype "output"))
    )
    (net (code "36") (name "/Main_E") (class "Default")
      (node (ref "J11") (pin "3") (pinfunction "3_3") (pintype "passive"))
      (node (ref "R11") (pin "1") (pinfunction "1_1") (pintype "passive"))
      (node (ref "R26") (pin "1") (pinfunction "1_1") (pintype "passive"))
      (node (ref "U6") (pin "12") (pinfunction "5C_12") (pintype "output"))
    )
    (net (code "37") (name "/Main_F") (class "Default")
      (node (ref "J11") (pin "5") (pinfunction "5_5") (pintype "passive"))
      (node (ref "R13") (pin "1") (pinfunction "1_1") (pintype "passive"))
      (node (ref "R28") (pin "1") (pinfunction "1_1") (pintype "passive"))
      (node (ref "U6") (pin "11") (pinfunction "6C_11") (pintype "output"))
    )
    (net (code "38") (name "/Main_G") (class "Default")
      (node (ref "J11") (pin "4") (pinfunction "4_4") (pintype "passive"))
      (node (ref "R14") (pin "1") (pinfunction "1_1") (pintype "passive"))
      (node (ref "R30") (pin "1") (pinfunction "1_1") (pintype "passive"))
      (node (ref "U6") (pin "10") (pinfunction "7C_10") (pintype "output"))
    )
    (net (code "39") (name "/RC_Node") (class "Default")
      (node (ref "C21") (pin "1") (pinfunction "POS_1") (pintype "passive"))
      (node (ref "C22") (pin "2") (pinfunction "2_2") (pintype "passive"))
      (node (ref "R44") (pin "1") (pinfunction "1_1") (pintype "passive"))
      (node (ref "U5") (pin "6") (pinfunction "THRESHOLD_6") (pintype "input"))
      (node (ref "U5") (pin "7") (pinfunction "DISCHARGE_7") (pintype "output"))
    )
    (net (code "40") (name "/RST") (class "Default")
      (node (ref "C1") (pin "2") (pinfunction "2_2") (pintype "passive"))
      (node (ref "J3") (pin "05") (pinfunction "05_05") (pintype "passive"))
      (node (ref "J6") (pin "02") (pinfunction "02_02") (pintype "passive"))
      (node (ref "R10") (pin "1") (pinfunction "1_1") (pintype "passive"))
      (node (ref "S2") (pin "1") (pinfunction "1_1") (pintype "passive"))
      (node (ref "U1") (pin "3") (pinfunction "EN_3") (pintype "input"))
    )
    (net (code "41") (name "/RX") (class "Default")
      (node (ref "J3") (pin "02") (pinfunction "02_02") (pintype "passive"))
      (node (ref "J5") (pin "2") (pinfunction "2_2") (pintype "passive"))
      (node (ref "U1") (pin "35") (pinfunction "TXD0_35") (pintype "bidirectional"))
    )
    (net (code "42") (name "/SCL_3") (class "Default")
      (node (ref "IC1") (pin "2") (pinfunction "SCL_2") (pintype "input"))
      (node (ref "R16") (pin "2") (pinfunction "2_2") (pintype "passive"))
      (node (ref "R35") (pin "2") (pinfunction "2_2") (pintype "passive"))
    )
    (net (code "43") (name "/SDA_3") (class "Default")
      (node (ref "IC1") (pin "3") (pinfunction "SDA_3") (pintype "input"))
      (node (ref "R17") (pin "2") (pinfunction "2_2") (pintype "passive"))
      (node (ref "R32") (pin "2") (pinfunction "2_2") (pintype "passive"))
    )
    (net (code "44") (name "/TX") (class "Default")
      (node (ref "J3") (pin "03") (pinfunction "03_03") (pintype "passive"))
      (node (ref "J5") (pin "3") (pinfunction "3_3") (pintype "passive"))
      (node (ref "U1") (pin "34") (pinfunction "RXD0_34") (pintype "bidirectional"))
    )
    (net (code "45") (name "/WDT_OUT") (class "Default")
      (node (ref "R38") (pin "1") (pinfunction "1_1") (pintype "passive"))
      (node (ref "U5") (pin "3") (pinfunction "OUTPUT_3") (pintype "output"))
    )
    (net (code "46") (name "/WDT_SW") (class "Default")
      (node (ref "J14") (pin "02") (pinfunction "02_02") (pintype "passive"))
      (node (ref "U5") (pin "4") (pinfunction "~{RESET}_4") (pintype "input"))
    )
    (net (code "47") (name "GND") (class "Default")
      (node (ref "1") (pin "4") (pinfunction "4_4") (pintype "bidirectional"))
      (node (ref "2") (pin "4") (pinfunction "4_4") (pintype "bidirectional"))
      (node (ref "C1") (pin "1") (pinfunction "1_1") (pintype "passive"))
      (node (ref "C12") (pin "1") (pinfunction "1_1") (pintype "passive"))
      (node (ref "C13") (pin "2") (pinfunction "2_2") (pintype "passive"))
      (node (ref "C15") (pin "1") (pinfunction "1_1") (pintype "passive"))
      (node (ref "C16") (pin "1") (pinfunction "1_1") (pintype "passive"))
      (node (ref "C17") (pin "2") (pinfunction "NEG_2") (pintype "passive"))
      (node (ref "C18") (pin "1") (pinfunction "1_1") (pintype "passive"))
      (node (ref "C19") (pin "2") (pinfunction "2_2") (pintype "passive"))
      (node (ref "C2") (pin "2") (pinfunction "2_2") (pintype "passive"))
      (node (ref "C20") (pin "2") (pinfunction "2_2") (pintype "passive"))
      (node (ref "C21") (pin "2") (pinfunction "NEG_2") (pintype "passive"))
      (node (ref "C22") (pin "1") (pinfunction "1_1") (pintype "passive"))
      (node (ref "C23") (pin "1") (pinfunction "1_1") (pintype "passive"))
      (node (ref "C3") (pin "2") (pinfunction "2_2") (pintype "passive"))
      (node (ref "C4") (pin "1") (pinfunction "1_1") (pintype "passive"))
      (node (ref "C5") (pin "2") (pinfunction "2_2") (pintype "passive"))
      (node (ref "C6") (pin "2") (pinfunction "2_2") (pintype "passive"))
      (node (ref "C7") (pin "1") (pinfunction "1_1") (pintype "passive"))
      (node (ref "C8") (pin "2") (pinfunction "2_2") (pintype "passive"))
      (node (ref "C9") (pin "2") (pinfunction "2_2") (pintype "passive"))
      (node (ref "D3") (pin "C") (pinfunction "C_C") (pintype "passive"))
      (node (ref "D5") (pin "C") (pinfunction "C_C") (pintype "passive"))
      (node (ref "D6") (pin "C") (pinfunction "C_C") (pintype "passive"))
      (node (ref "D7") (pin "C") (pinfunction "C_C") (pintype "passive"))
      (node (ref "D8") (pin "C") (pinfunction "C_C") (pintype "passive"))
      (node (ref "IC1") (pin "4") (pinfunction "GND_4") (pintype "power_in"))
      (node (ref "J10") (pin "2") (pinfunction "GND_2") (pintype "power_in"))
      (node (ref "J11") (pin "8") (pinfunction "8_8") (pintype "passive"))
      (node (ref "J12") (pin "3") (pinfunction "3_3") (pintype "passive"))
      (node (ref "J13") (pin "2") (pinfunction "2_2") (pintype "passive"))
      (node (ref "J14") (pin "03") (pinfunction "03_03") (pintype "passive"))
      (node (ref "J2") (pin "2") (pinfunction "2_2") (pintype "passive"))
      (node (ref "J3") (pin "06") (pinfunction "06_06") (pintype "passive"))
      (node (ref "J4") (pin "1") (pinfunction "1_1") (pintype "passive"))
      (node (ref "J5") (pin "4") (pinfunction "4_4") (pintype "passive"))
      (node (ref "Q1") (pin "2") (pinfunction "E_2") (pintype "passive"))
      (node (ref "Q3") (pin "2") (pinfunction "E_2") (pintype "passive"))
      (node (ref "Q5") (pin "2") (pinfunction "E_2") (pintype "passive"))
      (node (ref "Q6") (pin "2") (pinfunction "E_2") (pintype "passive"))
      (node (ref "S1") (pin "2") (pinfunction "2_2") (pintype "passive"))
      (node (ref "S2") (pin "2") (pinfunction "2_2") (pintype "passive"))
      (node (ref "U1") (pin "1") (pinfunction "GND_1") (pintype "power_in"))
      (node (ref "U1") (pin "15") (pinfunction "GND_15") (pintype "power_in"))
      (node (ref "U1") (pin "38") (pinfunction "GND_38") (pintype "power_in"))
      (node (ref "U1") (pin "39_1") (pinfunction "GND_39_1") (pintype "power_in"))
      (node (ref "U1") (pin "39_2") (pinfunction "GND_39_2") (pintype "power_in"))
      (node (ref "U1") (pin "39_3") (pinfunction "GND_39_3") (pintype "power_in"))
      (node (ref "U1") (pin "39_4") (pinfunction "GND_39_4") (pintype "power_in"))
      (node (ref "U1") (pin "39_5") (pinfunction "GND_39_5") (pintype "power_in"))
      (node (ref "U1") (pin "39_6") (pinfunction "GND_39_6") (pintype "power_in"))
      (node (ref "U1") (pin "39_7") (pinfunction "GND_39_7") (pintype "power_in"))
      (node (ref "U1") (pin "39_8") (pinfunction "GND_39_8") (pintype "power_in"))
      (node (ref "U1") (pin "39_9") (pinfunction "GND_39_9") (pintype "power_in"))
      (node (ref "U2") (pin "10") (pinfunction "GND_10") (pintype "power_in"))
      (node (ref "U2") (pin "7") (pinfunction "GND_7") (pintype "power_in"))
      (node (ref "U3") (pin "2") (pinfunction "C_2") (pintype "passive"))
      (node (ref "U3") (pin "3") (pinfunction "EMIT_3") (pintype "passive"))
      (node (ref "U4") (pin "2") (pinfunction "C_2") (pintype "passive"))
      (node (ref "U4") (pin "3") (pinfunction "EMIT_3") (pintype "passive"))
      (node (ref "U5") (pin "1") (pinfunction "GND_1") (pintype "passive"))
      (node (ref "U6") (pin "8") (pinfunction "E_8") (pintype "input"))
    )
    (net (code "48") (name "Net-(*1-2E)") (class "Default")
      (node (ref "*1") (pin "2") (pinfunction "2E_2") (pintype "input"))
      (node (ref "R11") (pin "2") (pinfunction "2_2") (pintype "passive"))
    )
    (net (code "49") (name "Net-(*1-3D)") (class "Default")
      (node (ref "*1") (pin "3") (pinfunction "3D_3") (pintype "input"))
      (node (ref "R8") (pin "2") (pinfunction "2_2") (pintype "passive"))
    )
    (net (code "50") (name "Net-(*1-4C)") (class "Default")
      (node (ref "*1") (pin "4") (pinfunction "4C_4") (pintype "input"))
      (node (ref "R6") (pin "2") (pinfunction "2_2") (pintype "passive"))
    )
    (net (code "51") (name "Net-(*1-5COM)") (class "Default")
      (node (ref "*1") (pin "5") (pinfunction "5COM_5") (pintype "input"))
      (node (ref "Q2") (pin "3") (pinfunction "D_3") (pintype "passive"))
    )
    (net (code "52") (name "Net-(*1-6B)") (class "Default")
      (node (ref "*1") (pin "6") (pinfunction "6B_6") (pintype "input"))
      (node (ref "R5") (pin "2") (pinfunction "2_2") (pintype "passive"))
    )
    (net (code "53") (name "Net-(*1-7A)") (class "Default")
      (node (ref "*1") (pin "7") (pinfunction "7A_7") (pintype "input"))
      (node (ref "R3") (pin "2") (pinfunction "2_2") (pintype "passive"))
    )
    (net (code "54") (name "Net-(*1-9F)") (class "Default")
      (node (ref "*1") (pin "9") (pinfunction "9F_9") (pintype "input"))
      (node (ref "R13") (pin "2") (pinfunction "2_2") (pintype "passive"))
    )
    (net (code "55") (name "Net-(*1-10G)") (class "Default")
      (node (ref "*1") (pin "10") (pinfunction "10G_10") (pintype "input"))
      (node (ref "R14") (pin "2") (pinfunction "2_2") (pintype "passive"))
    )
    (net (code "56") (name "Net-(*2-1COM)") (class "Default")
      (node (ref "*2") (pin "1") (pinfunction "1COM_1") (pintype "input"))
      (node (ref "Q4") (pin "3") (pinfunction "D_3") (pintype "passive"))
    )
    (net (code "57") (name "Net-(*2-2E)") (class "Default")
      (node (ref "*2") (pin "2") (pinfunction "2E_2") (pintype "input"))
      (node (ref "R26") (pin "2") (pinfunction "2_2") (pintype "passive"))
    )
    (net (code "58") (name "Net-(*2-3D)") (class "Default")
      (node (ref "*2") (pin "3") (pinfunction "3D_3") (pintype "input"))
      (node (ref "R24") (pin "2") (pinfunction "2_2") (pintype "passive"))
    )
    (net (code "59") (name "Net-(*2-4C)") (class "Default")
      (node (ref "*2") (pin "4") (pinfunction "4C_4") (pintype "input"))
      (node (ref "R23") (pin "2") (pinfunction "2_2") (pintype "passive"))
    )
    (net (code "60") (name "Net-(*2-6B)") (class "Default")
      (node (ref "*2") (pin "6") (pinfunction "6B_6") (pintype "input"))
      (node (ref "R22") (pin "2") (pinfunction "2_2") (pintype "passive"))
    )
    (net (code "61") (name "Net-(*2-7A)") (class "Default")
      (node (ref "*2") (pin "7") (pinfunction "7A_7") (pintype "input"))
      (node (ref "R21") (pin "2") (pinfunction "2_2") (pintype "passive"))
    )
    (net (code "62") (name "Net-(*2-9F)") (class "Default")
      (node (ref "*2") (pin "9") (pinfunction "9F_9") (pintype "input"))
      (node (ref "R28") (pin "2") (pinfunction "2_2") (pintype "passive"))
    )
    (net (code "63") (name "Net-(*2-10G)") (class "Default")
      (node (ref "*2") (pin "10") (pinfunction "10G_10") (pintype "input"))
      (node (ref "R30") (pin "2") (pinfunction "2_2") (pintype "passive"))
    )
    (net (code "64") (name "Net-(C17-POS)") (class "Default")
      (node (ref "C14") (pin "1") (pinfunction "1_1") (pintype "passive"))
      (node (ref "C17") (pin "1") (pinfunction "POS_1") (pintype "passive"))
      (node (ref "C18") (pin "2") (pinfunction "2_2") (pintype "passive"))
      (node (ref "J10") (pin "3") (pinfunction "VCC_3") (pintype "power_in"))
    )
    (net (code "65") (name "Net-(D3-PadA)") (class "Default")
      (node (ref "D3") (pin "A") (pinfunction "A_A") (pintype "passive"))
      (node (ref "R20") (pin "2") (pinfunction "2_2") (pintype "passive"))
    )
    (net (code "66") (name "Net-(D5-PadA)") (class "Default")
      (node (ref "D5") (pin "A") (pinfunction "A_A") (pintype "passive"))
      (node (ref "R36") (pin "2") (pinfunction "2_2") (pintype "passive"))
    )
    (net (code "67") (name "Net-(D6-PadA)") (class "Default")
      (node (ref "D6") (pin "A") (pinfunction "A_A") (pintype "passive"))
      (node (ref "R37") (pin "2") (pinfunction "2_2") (pintype "passive"))
    )
    (net (code "68") (name "Net-(D7-PadA)") (class "Default")
      (node (ref "D7") (pin "A") (pinfunction "A_A") (pintype "passive"))
      (node (ref "R39") (pin "2") (pinfunction "2_2") (pintype "passive"))
    )
    (net (code "69") (name "Net-(D8-PadA)") (class "Default")
      (node (ref "D8") (pin "A") (pinfunction "A_A") (pintype "passive"))
      (node (ref "R40") (pin "2") (pinfunction "2_2") (pintype "passive"))
    )
    (net (code "70") (name "Net-(J14-Pad01)") (class "Default")
      (node (ref "J14") (pin "01") (pinfunction "01_01") (pintype "passive"))
      (node (ref "R47") (pin "2") (pinfunction "2_2") (pintype "passive"))
    )
    (net (code "71") (name "Net-(Q1-B)") (class "Default")
      (node (ref "Q1") (pin "1") (pinfunction "B_1") (pintype "passive"))
      (node (ref "R1") (pin "2") (pinfunction "2_2") (pintype "passive"))
    )
    (net (code "72") (name "Net-(Q1-C)") (class "Default")
      (node (ref "D1") (pin "A") (pinfunction "A_A") (pintype "passive"))
      (node (ref "J1") (pin "2") (pinfunction "2_2") (pintype "passive"))
      (node (ref "Q1") (pin "3") (pinfunction "C_3") (pintype "passive"))
    )
    (net (code "73") (name "Net-(Q2-G)") (class "Default")
      (node (ref "D2") (pin "A") (pinfunction "A_A") (pintype "passive"))
      (node (ref "Q2") (pin "1") (pinfunction "G_1") (pintype "passive"))
      (node (ref "R19") (pin "1") (pinfunction "1_1") (pintype "passive"))
    )
    (net (code "74") (name "Net-(Q3-B)") (class "Default")
      (node (ref "Q3") (pin "1") (pinfunction "B_1") (pintype "passive"))
      (node (ref "R15") (pin "1") (pinfunction "1_1") (pintype "passive"))
    )
    (net (code "75") (name "Net-(Q3-C)") (class "Default")
      (node (ref "Q3") (pin "3") (pinfunction "C_3") (pintype "passive"))
      (node (ref "R19") (pin "2") (pinfunction "2_2") (pintype "passive"))
    )
    (net (code "76") (name "Net-(Q4-G)") (class "Default")
      (node (ref "D4") (pin "A") (pinfunction "A_A") (pintype "passive"))
      (node (ref "Q4") (pin "1") (pinfunction "G_1") (pintype "passive"))
      (node (ref "R33") (pin "2") (pinfunction "2_2") (pintype "passive"))
      (node (ref "R34") (pin "1") (pinfunction "1_1") (pintype "passive"))
    )
    (net (code "77") (name "Net-(Q5-B)") (class "Default")
      (node (ref "Q5") (pin "1") (pinfunction "B_1") (pintype "passive"))
      (node (ref "R31") (pin "1") (pinfunction "1_1") (pintype "passive"))
    )
    (net (code "78") (name "Net-(Q5-C)") (class "Default")
      (node (ref "Q5") (pin "3") (pinfunction "C_3") (pintype "passive"))
      (node (ref "R34") (pin "2") (pinfunction "2_2") (pintype "passive"))
    )
    (net (code "79") (name "Net-(Q6-B)") (class "Default")
      (node (ref "Q6") (pin "1") (pinfunction "B_1") (pintype "passive"))
      (node (ref "R38") (pin "2") (pinfunction "2_2") (pintype "passive"))
    )
    (net (code "80") (name "Net-(Q6-C)") (class "Default")
      (node (ref "J6") (pin "01") (pinfunction "01_01") (pintype "passive"))
      (node (ref "Q6") (pin "3") (pinfunction "C_3") (pintype "passive"))
    )
    (net (code "81") (name "Net-(U1-IO2)") (class "Default")
      (node (ref "R20") (pin "1") (pinfunction "1_1") (pintype "passive"))
      (node (ref "U1") (pin "24") (pinfunction "IO2_24") (pintype "bidirectional"))
    )
    (net (code "82") (name "Net-(U1-IO15)") (class "Default")
      (node (ref "R25") (pin "1") (pinfunction "1_1") (pintype "passive"))
      (node (ref "U1") (pin "23") (pinfunction "IO15_23") (pintype "bidirectional"))
    )
    (net (code "83") (name "Net-(U1-IO16)") (class "Default")
      (node (ref "R27") (pin "1") (pinfunction "1_1") (pintype "passive"))
      (node (ref "U1") (pin "27") (pinfunction "IO16_27") (pintype "bidirectional"))
    )
    (net (code "84") (name "Net-(U1-IO17)") (class "Default")
      (node (ref "R29") (pin "1") (pinfunction "1_1") (pintype "passive"))
      (node (ref "U1") (pin "28") (pinfunction "IO17_28") (pintype "bidirectional"))
    )
    (net (code "85") (name "Net-(U1-IO21)") (class "Default")
      (node (ref "R32") (pin "1") (pinfunction "1_1") (pintype "passive"))
      (node (ref "U1") (pin "33") (pinfunction "IO21_33") (pintype "bidirectional"))
    )
    (net (code "86") (name "Net-(U1-IO22)") (class "Default")
      (node (ref "R35") (pin "1") (pinfunction "1_1") (pintype "passive"))
      (node (ref "U1") (pin "36") (pinfunction "IO22_36") (pintype "bidirectional"))
    )
    (net (code "87") (name "Net-(U2-SPK1)") (class "Default")
      (node (ref "J9") (pin "02") (pinfunction "02_02") (pintype "passive"))
      (node (ref "U2") (pin "6") (pinfunction "SPK1_6") (pintype "passive"))
    )
    (net (code "88") (name "Net-(U2-SPK2)") (class "Default")
      (node (ref "J9") (pin "01") (pinfunction "01_01") (pintype "passive"))
      (node (ref "U2") (pin "8") (pinfunction "SPK2_8") (pintype "passive"))
    )
    (net (code "89") (name "Net-(U3-A)") (class "Default")
      (node (ref "R41") (pin "2") (pinfunction "2_2") (pintype "passive"))
      (node (ref "U3") (pin "1") (pinfunction "A_1") (pintype "passive"))
    )
    (net (code "90") (name "Net-(U4-A)") (class "Default")
      (node (ref "R42") (pin "2") (pinfunction "2_2") (pintype "passive"))
      (node (ref "U4") (pin "1") (pinfunction "A_1") (pintype "passive"))
    )
    (net (code "91") (name "Net-(U5-CONTROL_VOLTAGE)") (class "Default")
      (node (ref "C23") (pin "2") (pinfunction "2_2") (pintype "passive"))
      (node (ref "U5") (pin "5") (pinfunction "CONTROL_VOLTAGE_5") (pintype "input"))
    )
    (net (code "92") (name "Net-(U5-~{TRIGGER})") (class "Default")
      (node (ref "R45") (pin "1") (pinfunction "1_1") (pintype "passive"))
      (node (ref "R46") (pin "2") (pinfunction "2_2") (pintype "passive"))
      (node (ref "U5") (pin "2") (pinfunction "~{TRIGGER}_2") (pintype "input"))
    )
    (net (code "93") (name "unconnected-(*1-1COM-Pad1)") (class "Default")
      (node (ref "*1") (pin "1") (pinfunction "1COM_1") (pintype "input+no_connect"))
    )
    (net (code "94") (name "unconnected-(*1-8DP-Pad8)") (class "Default")
      (node (ref "*1") (pin "8") (pinfunction "8DP_8") (pintype "input+no_connect"))
    )
    (net (code "95") (name "unconnected-(*2-5COM-Pad5)") (class "Default")
      (node (ref "*2") (pin "5") (pinfunction "5COM_5") (pintype "input+no_connect"))
    )
    (net (code "96") (name "unconnected-(*2-8DP-Pad8)") (class "Default")
      (node (ref "*2") (pin "8") (pinfunction "8DP_8") (pintype "input+no_connect"))
    )
    (net (code "97") (name "unconnected-(IC1-DP{slash}KP-Pad16)") (class "Default")
      (node (ref "IC1") (pin "16") (pinfunction "DP/KP_16") (pintype "bidirectional+no_connect"))
    )
    (net (code "98") (name "unconnected-(J2-Pad3)") (class "Default")
      (node (ref "J2") (pin "3") (pinfunction "3_3") (pintype "passive"))
    )
    (net (code "99") (name "unconnected-(J4-Pad4)") (class "Default")
      (node (ref "J4") (pin "4") (pinfunction "4_4") (pintype "passive"))
    )
    (net (code "100") (name "unconnected-(J4-Pad5)") (class "Default")
      (node (ref "J4") (pin "5") (pinfunction "5_5") (pintype "passive"))
    )
    (net (code "101") (name "unconnected-(J13-Pad4)") (class "Default")
      (node (ref "J13") (pin "4") (pinfunction "4_4") (pintype "passive+no_connect"))
    )
    (net (code "102") (name "unconnected-(U1-IO4-Pad26)") (class "Default")
      (node (ref "U1") (pin "26") (pinfunction "IO4_26") (pintype "bidirectional+no_connect"))
    )
    (net (code "103") (name "unconnected-(U1-IO12-Pad14)") (class "Default")
      (node (ref "U1") (pin "14") (pinfunction "IO12_14") (pintype "bidirectional+no_connect"))
    )
    (net (code "104") (name "unconnected-(U1-IO13-Pad16)") (class "Default")
      (node (ref "U1") (pin "16") (pinfunction "IO13_16") (pintype "bidirectional+no_connect"))
    )
    (net (code "105") (name "unconnected-(U1-IO14-Pad13)") (class "Default")
      (node (ref "U1") (pin "13") (pinfunction "IO14_13") (pintype "bidirectional+no_connect"))
    )
    (net (code "106") (name "unconnected-(U1-IO19-Pad31)") (class "Default")
      (node (ref "U1") (pin "31") (pinfunction "IO19_31") (pintype "bidirectional+no_connect"))
    )
    (net (code "107") (name "unconnected-(U1-IO23-Pad37)") (class "Default")
      (node (ref "U1") (pin "37") (pinfunction "IO23_37") (pintype "bidirectional+no_connect"))
    )
    (net (code "108") (name "unconnected-(U1-IO26-Pad11)") (class "Default")
      (node (ref "U1") (pin "11") (pinfunction "IO26_11") (pintype "bidirectional+no_connect"))
    )
    (net (code "109") (name "unconnected-(U1-IO32-Pad8)") (class "Default")
      (node (ref "U1") (pin "8") (pinfunction "IO32_8") (pintype "bidirectional+no_connect"))
    )
    (net (code "110") (name "unconnected-(U1-IO33-Pad9)") (class "Default")
      (node (ref "U1") (pin "9") (pinfunction "IO33_9") (pintype "bidirectional+no_connect"))
    )
    (net (code "111") (name "unconnected-(U1-NC-Pad32)") (class "Default")
      (node (ref "U1") (pin "32") (pinfunction "NC_32") (pintype "passive+no_connect"))
    )
    (net (code "112") (name "unconnected-(U1-SCK{slash}CLK-Pad20)") (class "Default")
      (node (ref "U1") (pin "20") (pinfunction "SCK/CLK_20") (pintype "bidirectional+no_connect"))
    )
    (net (code "113") (name "unconnected-(U1-SCS{slash}CMD-Pad19)") (class "Default")
      (node (ref "U1") (pin "19") (pinfunction "SCS/CMD_19") (pintype "bidirectional+no_connect"))
    )
    (net (code "114") (name "unconnected-(U1-SDI{slash}SD1-Pad22)") (class "Default")
      (node (ref "U1") (pin "22") (pinfunction "SDI/SD1_22") (pintype "bidirectional+no_connect"))
    )
    (net (code "115") (name "unconnected-(U1-SDO{slash}SD0-Pad21)") (class "Default")
      (node (ref "U1") (pin "21") (pinfunction "SDO/SD0_21") (pintype "bidirectional+no_connect"))
    )
    (net (code "116") (name "unconnected-(U1-SHD{slash}SD2-Pad17)") (class "Default")
      (node (ref "U1") (pin "17") (pinfunction "SHD/SD2_17") (pintype "bidirectional+no_connect"))
    )
    (net (code "117") (name "unconnected-(U1-SWP{slash}SD3-Pad18)") (class "Default")
      (node (ref "U1") (pin "18") (pinfunction "SWP/SD3_18") (pintype "bidirectional+no_connect"))
    )
    (net (code "118") (name "unconnected-(U2-ADKEY1-Pad12)") (class "Default")
      (node (ref "U2") (pin "12") (pinfunction "ADKEY1_12") (pintype "input+no_connect"))
    )
    (net (code "119") (name "unconnected-(U2-ADKEY2-Pad13)") (class "Default")
      (node (ref "U2") (pin "13") (pinfunction "ADKEY2_13") (pintype "input+no_connect"))
    )
    (net (code "120") (name "unconnected-(U2-IO1-Pad9)") (class "Default")
      (node (ref "U2") (pin "9") (pinfunction "IO1_9") (pintype "bidirectional+no_connect"))
    )
    (net (code "121") (name "unconnected-(U2-IO2-Pad11)") (class "Default")
      (node (ref "U2") (pin "11") (pinfunction "IO2_11") (pintype "bidirectional+no_connect"))
    )
    (net (code "122") (name "unconnected-(U2-USB+-Pad14)") (class "Default")
      (node (ref "U2") (pin "14") (pinfunction "USB+_14") (pintype "input+no_connect"))
    )
    (net (code "123") (name "unconnected-(U2-USB--Pad15)") (class "Default")
      (node (ref "U2") (pin "15") (pinfunction "USB-_15") (pintype "input+no_connect"))
    )
    (net (code "124") (name "unconnected-(U6-COM-Pad9)") (class "Default")
      (node (ref "U6") (pin "9") (pinfunction "COM_9") (pintype "output+no_connect"))
    )
  )
)
